# 3_cyber60-2-mcu.net
KiCad netlist of a schematic drawn in Altium Designer
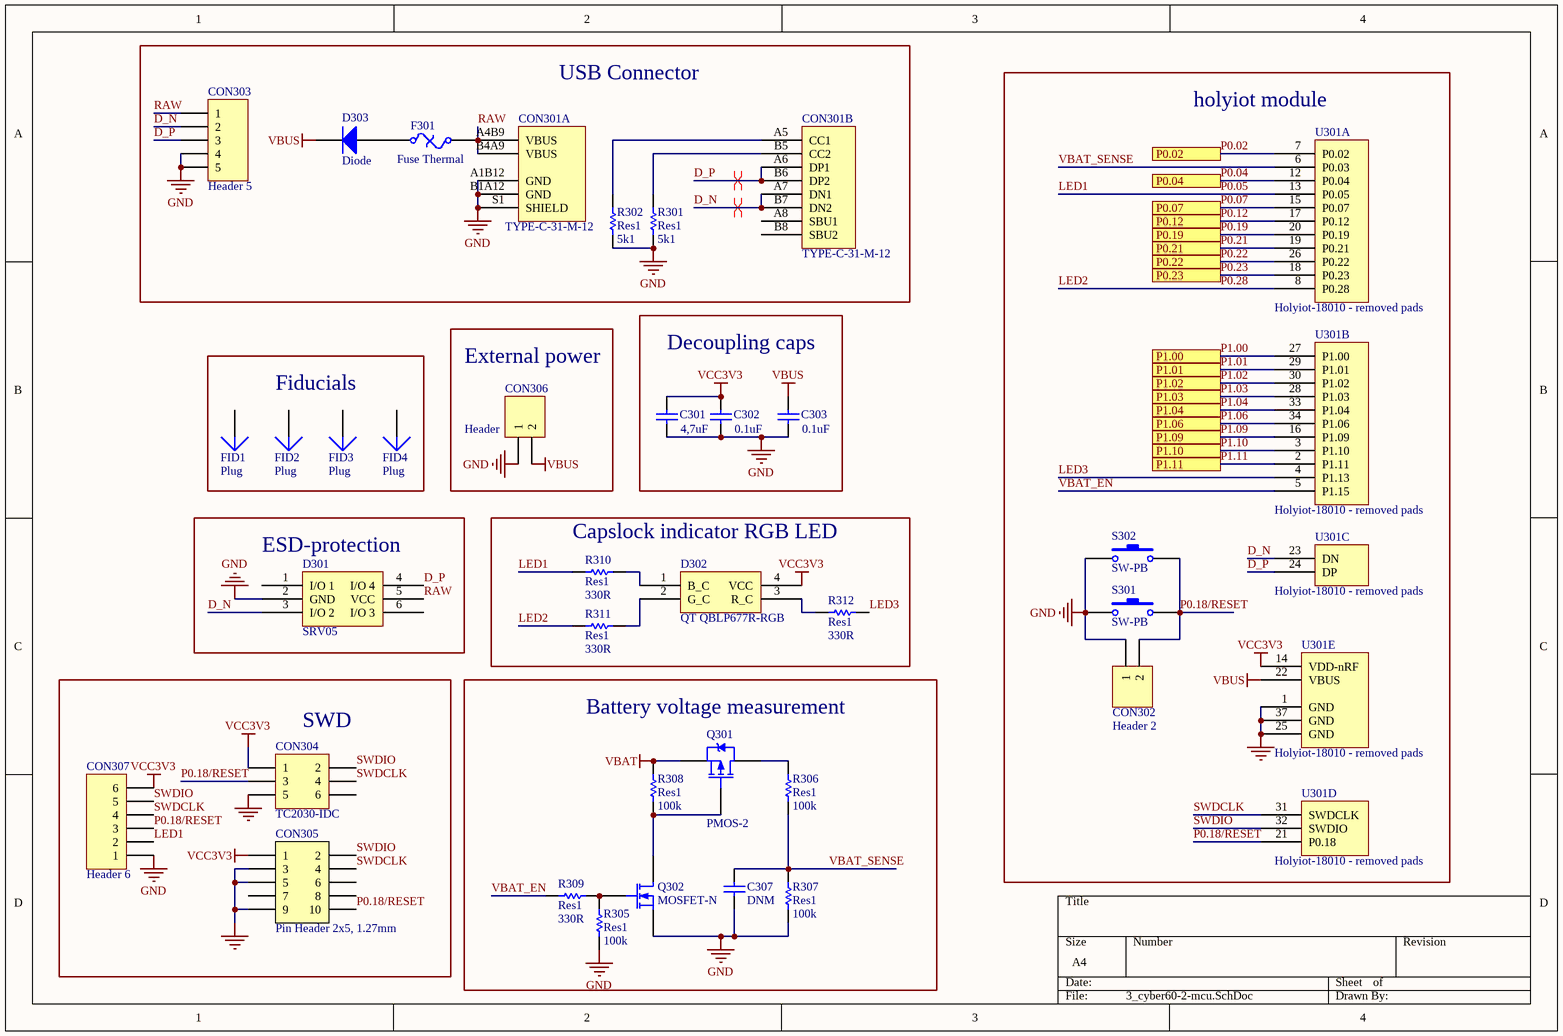
[diagram p0: 3_cyber60-2-mcu.SchDoc]

(export (version "E")
  (design (tool "Eeschema 10.0.6"))
  (components
    (comp (ref "C301")
      (value "4,7uF")
      (footprint "C0603[1608]")
      (description "Capacitor")
      (fields (field (name "LCSC PART #") "C19666") (field (name "MRF.PART") "CL10A475KO8NNNC"))
      (libsource (lib "Miscellaneous Devices") (part "Cap"))
    )
    (comp (ref "C302")
      (value "0.1uF")
      (footprint "C0603[1608]")
      (description "Capacitor")
      (fields (field (name "MFG") "KEMET") (field (name "LCSC PART #") "C14663"))
      (libsource (lib "Miscellaneous Devices") (part "Cap"))
    )
    (comp (ref "C303")
      (value "0.1uF")
      (footprint "C0603[1608]")
      (description "Capacitor")
      (fields (field (name "MFG") "KEMET") (field (name "LCSC PART #") "C14663"))
      (libsource (lib "Miscellaneous Devices") (part "Cap"))
    )
    (comp (ref "C307")
      (value "DNM")
      (footprint "C0603[1608]")
      (description "Capacitor")
      (libsource (lib "Miscellaneous Devices") (part "Cap"))
    )
    (comp (ref "CON301")
      (value "TYPE-C-31-M-12")
      (footprint "TYPE-C-31-M-12")
      (fields (field (name "MFG") "Korean Hroparts Elec") (field (name "LCSC PART #") "C165948"))
      (libsource (lib "Schlib1") (part "TYPE-C-31-M-12"))
    )
    (comp (ref "CON302")
      (value "Header 2")
      (footprint "HDR1X2")
      (description "Header, 2-Pin")
      (libsource (lib "Miscellaneous Connectors") (part "Header 2"))
    )
    (comp (ref "CON303")
      (value "Header 5")
      (footprint "JST SM04B-SRSS-TB")
      (description "JST for USB daughter board")
      (fields (field (name "MFG") "JST Sales America Inc.") (field (name "LCSC PART #") "C160404"))
      (libsource (lib "Miscellaneous Connectors") (part "Header 5"))
    )
    (comp (ref "CON304")
      (value "TC2030-IDC")
      (footprint "TC2030-IDC-NL")
      (description "Header, 3-Pin, Dual row")
      (libsource (lib "Miscellaneous Connectors") (part "Header 3X2"))
    )
    (comp (ref "CON305")
      (value "Pin Header 2x5, 1.27mm")
      (footprint "HDR_2x5-SMD-1.27mm-K")
      (description "Pin Header 2x5, 1.27mm (50mil), SMD, Keying Shroud")
      (fields (field (name "MFG") "Samtec Inc."))
      (libsource (lib "Nordic Passive DB") (part "CONN-2x5"))
    )
    (comp (ref "CON306")
      (value "Header")
      (footprint "HDR1X2")
      (description "Header, 2-Pin")
      (libsource (lib "") (part "Header 2_1"))
    )
    (comp (ref "CON307")
      (value "Header 6")
      (footprint "HDR1X6")
      (description "Header, 6-Pin")
      (fields (field (name "PUBLISHER") "Altium Limited"))
      (libsource (lib "Miscellaneous Connectors") (part "Header 6"))
    )
    (comp (ref "D301")
      (value "SRV05")
      (footprint "SOT-23-6")
      (fields (field (name "LCSC PART #") "C85364") (field (name "MRF.PART") "SRV05-4-P-T7"))
      (libsource (lib "Keebs") (part "SRV05"))
    )
    (comp (ref "D302")
      (value "QT QBLP677R-RGB")
      (footprint "QT QBLP677R-RGB")
      (description "RGB LED")
      (fields (field (name "MFG") "QT Brightek (QTB)"))
      (libsource (lib "Keebs") (part "QT QBLP677R-RGB"))
    )
    (comp (ref "D303")
      (value "Diode")
      (footprint "SOD-123")
      (description "Default Diode")
      (fields (field (name "LCSC PART #") "C8598") (field (name "MRF.PART") "B5819W"))
      (libsource (lib "Miscellaneous Devices") (part "Diode"))
    )
    (comp (ref "F301")
      (value "Fuse Thermal")
      (footprint "C1206[3216]")
      (description "Thermal Fuse")
      (fields (field (name "MFG") "Bel Fuse Inc.") (field (name "LCSC PART #") "C135338"))
      (libsource (lib "Miscellaneous Devices") (part "Fuse Thermal"))
    )
    (comp (ref "FID1")
      (value "Plug")
      (footprint "Fiducial_Nordic")
      (libsource (lib "Miscellaneous Connectors") (part "Plug"))
    )
    (comp (ref "FID2")
      (value "Plug")
      (footprint "Fiducial_Nordic")
      (libsource (lib "Miscellaneous Connectors") (part "Plug"))
    )
    (comp (ref "FID3")
      (value "Plug")
      (footprint "Fiducial_Nordic")
      (libsource (lib "Miscellaneous Connectors") (part "Plug"))
    )
    (comp (ref "FID4")
      (value "Plug")
      (footprint "Fiducial_Nordic")
      (libsource (lib "Miscellaneous Connectors") (part "Plug"))
    )
    (comp (ref "Q301")
      (value "PMOS-2")
      (footprint "SOT-23-3")
      (description "P-Channel Power MOSFET")
      (fields (field (name "MRF.PART") "SI2301CDS-T1-GE3") (field (name "LCSC PART #") "C10487"))
      (libsource (lib "Miscellaneous Devices") (part "PMOS-2"))
    )
    (comp (ref "Q302")
      (value "MOSFET-N")
      (footprint "SOT-23-3")
      (description "N-Channel MOSFET")
      (fields (field (name "LCSC PART #") "C8545") (field (name "MRF.PART") "2N7002"))
      (libsource (lib "Miscellaneous Devices") (part "MOSFET-N"))
    )
    (comp (ref "R301")
      (value "Res1")
      (footprint "R0603[1608]")
      (description "Resistor")
      (fields
        (field (name "ALTIUM_VALUE") "5k1")
        (field (name "MFG") "Panasonic Electronic Components")
        (field (name "LCSC PART #") "C23186")
      )
      (libsource (lib "Miscellaneous Devices") (part "Res1"))
    )
    (comp (ref "R302")
      (value "Res1")
      (footprint "R0603[1608]")
      (description "Resistor")
      (fields
        (field (name "ALTIUM_VALUE") "5k1")
        (field (name "MFG") "Panasonic Electronic Components")
        (field (name "LCSC PART #") "C23186")
      )
      (libsource (lib "Miscellaneous Devices") (part "Res1"))
    )
    (comp (ref "R305")
      (value "Res1")
      (footprint "R0603[1608]")
      (description "Resistor")
      (fields
        (field (name "ALTIUM_VALUE") "100k")
        (field (name "MRF.PART") "0603WAF1003T5E")
        (field (name "LCSC PART #") "C25803")
      )
      (libsource (lib "Miscellaneous Devices") (part "Res1"))
    )
    (comp (ref "R306")
      (value "Res1")
      (footprint "R0603[1608]")
      (description "Resistor")
      (fields
        (field (name "ALTIUM_VALUE") "100k")
        (field (name "MRF.PART") "0603WAF1003T5E")
        (field (name "LCSC PART #") "C25803")
      )
      (libsource (lib "Miscellaneous Devices") (part "Res1"))
    )
    (comp (ref "R307")
      (value "Res1")
      (footprint "R0603[1608]")
      (description "Resistor")
      (fields
        (field (name "ALTIUM_VALUE") "100k")
        (field (name "MRF.PART") "0603WAF1003T5E")
        (field (name "LCSC PART #") "C25803")
      )
      (libsource (lib "Miscellaneous Devices") (part "Res1"))
    )
    (comp (ref "R308")
      (value "Res1")
      (footprint "R0603[1608]")
      (description "Resistor")
      (fields
        (field (name "ALTIUM_VALUE") "100k")
        (field (name "MRF.PART") "0603WAF1003T5E")
        (field (name "LCSC PART #") "C25803")
      )
      (libsource (lib "Miscellaneous Devices") (part "Res1"))
    )
    (comp (ref "R309")
      (value "Res1")
      (footprint "R0603[1608]")
      (description "Resistor")
      (fields
        (field (name "ALTIUM_VALUE") "330R")
        (field (name "LCSC PART #") "C23138")
        (field (name "MRF.PART") "0603WAF3300T5E")
      )
      (libsource (lib "Miscellaneous Devices") (part "Res1"))
    )
    (comp (ref "R310")
      (value "Res1")
      (footprint "R0603[1608]")
      (description "Resistor")
      (fields
        (field (name "ALTIUM_VALUE") "330R")
        (field (name "LCSC PART #") "C23138")
        (field (name "MRF.PART") "0603WAF3300T5E")
      )
      (libsource (lib "Miscellaneous Devices") (part "Res1"))
    )
    (comp (ref "R311")
      (value "Res1")
      (footprint "R0603[1608]")
      (description "Resistor")
      (fields
        (field (name "ALTIUM_VALUE") "330R")
        (field (name "LCSC PART #") "C23138")
        (field (name "MRF.PART") "0603WAF3300T5E")
      )
      (libsource (lib "Miscellaneous Devices") (part "Res1"))
    )
    (comp (ref "R312")
      (value "Res1")
      (footprint "R0603[1608]")
      (description "Resistor")
      (fields
        (field (name "ALTIUM_VALUE") "330R")
        (field (name "LCSC PART #") "C23138")
        (field (name "MRF.PART") "0603WAF3300T5E")
      )
      (libsource (lib "Miscellaneous Devices") (part "Res1"))
    )
    (comp (ref "S301")
      (value "SW-PB")
      (footprint "XKB Switch")
      (description "Switch")
      (fields (field (name "MFG") "C&K") (field (name "MRF.PART") "TS-1187A-C-D-B"))
      (libsource (lib "Miscellaneous Devices") (part "SW-PB"))
    )
    (comp (ref "S302")
      (value "SW-PB")
      (footprint "XKB Switch")
      (description "Switch")
      (fields (field (name "MFG") "C&K") (field (name "MRF.PART") "TS-1187A-C-D-B"))
      (libsource (lib "Miscellaneous Devices") (part "SW-PB"))
    )
    (comp (ref "U301")
      (value "Holyiot-18010 - removed pads")
      (footprint "Holyiot-18010 - removed pads")
      (libsource (lib "Keebs") (part "Holyiot-18010 - removed pads"))
    )
  )
  (nets
    (net (code "1") (name "/D_N") (class "Default")
      (node (ref "CON301") (pin "A7") (pinfunction "DN1_A7") (pintype "passive"))
      (node (ref "CON301") (pin "B7") (pinfunction "DN2_B7") (pintype "passive"))
      (node (ref "CON303") (pin "2") (pinfunction "2_2") (pintype "passive"))
      (node (ref "D301") (pin "3") (pinfunction "I/O_2_3") (pintype "passive"))
      (node (ref "U301") (pin "23") (pinfunction "DN_23") (pintype "passive"))
    )
    (net (code "2") (name "/D_P") (class "Default")
      (node (ref "CON301") (pin "A6") (pinfunction "DP1_A6") (pintype "passive"))
      (node (ref "CON301") (pin "B6") (pinfunction "DP2_B6") (pintype "passive"))
      (node (ref "CON303") (pin "3") (pinfunction "3_3") (pintype "passive"))
      (node (ref "D301") (pin "4") (pinfunction "I/O_4_4") (pintype "passive"))
      (node (ref "U301") (pin "24") (pinfunction "DP_24") (pintype "passive"))
    )
    (net (code "3") (name "/LED1") (class "Default")
      (node (ref "CON307") (pin "2") (pinfunction "2_2") (pintype "passive"))
      (node (ref "R310") (pin "2") (pinfunction "2_2") (pintype "passive"))
      (node (ref "U301") (pin "13") (pinfunction "P0.05_13") (pintype "passive"))
    )
    (net (code "4") (name "/LED2") (class "Default")
      (node (ref "R311") (pin "2") (pinfunction "2_2") (pintype "passive"))
      (node (ref "U301") (pin "8") (pinfunction "P0.28_8") (pintype "passive"))
    )
    (net (code "5") (name "/LED3") (class "Default")
      (node (ref "R312") (pin "1") (pinfunction "1_1") (pintype "passive"))
      (node (ref "U301") (pin "4") (pinfunction "P1.13_4") (pintype "passive"))
    )
    (net (code "6") (name "/P0.02") (class "Default")
      (node (ref "U301") (pin "7") (pinfunction "P0.02_7") (pintype "passive"))
    )
    (net (code "7") (name "/P0.04") (class "Default")
      (node (ref "U301") (pin "12") (pinfunction "P0.04_12") (pintype "passive"))
    )
    (net (code "8") (name "/P0.07") (class "Default")
      (node (ref "U301") (pin "15") (pinfunction "P0.07_15") (pintype "passive"))
    )
    (net (code "9") (name "/P0.12") (class "Default")
      (node (ref "U301") (pin "17") (pinfunction "P0.12_17") (pintype "passive"))
    )
    (net (code "10") (name "/P0.18{slash}RESET") (class "Default")
      (node (ref "CON302") (pin "2") (pinfunction "2_2") (pintype "passive"))
      (node (ref "CON304") (pin "3") (pinfunction "3_3") (pintype "passive"))
      (node (ref "CON305") (pin "10") (pinfunction "10_10") (pintype "passive"))
      (node (ref "CON307") (pin "3") (pinfunction "3_3") (pintype "passive"))
      (node (ref "S301") (pin "2") (pinfunction "2_2") (pintype "passive"))
      (node (ref "S302") (pin "1") (pinfunction "1_1") (pintype "passive"))
      (node (ref "U301") (pin "21") (pinfunction "P0.18_21") (pintype "passive"))
    )
    (net (code "11") (name "/P0.19") (class "Default")
      (node (ref "U301") (pin "20") (pinfunction "P0.19_20") (pintype "passive"))
    )
    (net (code "12") (name "/P0.21") (class "Default")
      (node (ref "U301") (pin "19") (pinfunction "P0.21_19") (pintype "passive"))
    )
    (net (code "13") (name "/P0.22") (class "Default")
      (node (ref "U301") (pin "26") (pinfunction "P0.22_26") (pintype "passive"))
    )
    (net (code "14") (name "/P0.23") (class "Default")
      (node (ref "U301") (pin "18") (pinfunction "P0.23_18") (pintype "passive"))
    )
    (net (code "15") (name "/P1.00") (class "Default")
      (node (ref "U301") (pin "27") (pinfunction "P1.00_27") (pintype "passive"))
    )
    (net (code "16") (name "/P1.01") (class "Default")
      (node (ref "U301") (pin "29") (pinfunction "P1.01_29") (pintype "passive"))
    )
    (net (code "17") (name "/P1.02") (class "Default")
      (node (ref "U301") (pin "30") (pinfunction "P1.02_30") (pintype "passive"))
    )
    (net (code "18") (name "/P1.03") (class "Default")
      (node (ref "U301") (pin "28") (pinfunction "P1.03_28") (pintype "passive"))
    )
    (net (code "19") (name "/P1.04") (class "Default")
      (node (ref "U301") (pin "33") (pinfunction "P1.04_33") (pintype "passive"))
    )
    (net (code "20") (name "/P1.06") (class "Default")
      (node (ref "U301") (pin "34") (pinfunction "P1.06_34") (pintype "passive"))
    )
    (net (code "21") (name "/P1.09") (class "Default")
      (node (ref "U301") (pin "16") (pinfunction "P1.09_16") (pintype "passive"))
    )
    (net (code "22") (name "/P1.10") (class "Default")
      (node (ref "U301") (pin "3") (pinfunction "P1.10_3") (pintype "passive"))
    )
    (net (code "23") (name "/P1.11") (class "Default")
      (node (ref "U301") (pin "2") (pinfunction "P1.11_2") (pintype "passive"))
    )
    (net (code "24") (name "/RAW") (class "Default")
      (node (ref "CON301") (pin "A4B9") (pinfunction "VBUS_A4B9") (pintype "passive"))
      (node (ref "CON301") (pin "B4A9") (pinfunction "VBUS_B4A9") (pintype "passive"))
      (node (ref "CON303") (pin "1") (pinfunction "1_1") (pintype "passive"))
      (node (ref "D301") (pin "5") (pinfunction "VCC_5") (pintype "passive"))
      (node (ref "F301") (pin "2") (pinfunction "2_2") (pintype "passive"))
    )
    (net (code "25") (name "/SWDCLK") (class "Default")
      (node (ref "CON304") (pin "4") (pinfunction "4_4") (pintype "passive"))
      (node (ref "CON305") (pin "4") (pinfunction "4_4") (pintype "passive"))
      (node (ref "CON307") (pin "4") (pinfunction "4_4") (pintype "passive"))
      (node (ref "U301") (pin "31") (pinfunction "SWDCLK_31") (pintype "passive"))
    )
    (net (code "26") (name "/SWDIO") (class "Default")
      (node (ref "CON304") (pin "2") (pinfunction "2_2") (pintype "passive"))
      (node (ref "CON305") (pin "2") (pinfunction "2_2") (pintype "passive"))
      (node (ref "CON307") (pin "5") (pinfunction "5_5") (pintype "passive"))
      (node (ref "U301") (pin "32") (pinfunction "SWDIO_32") (pintype "passive"))
    )
    (net (code "27") (name "/VBAT_EN") (class "Default")
      (node (ref "R309") (pin "2") (pinfunction "2_2") (pintype "passive"))
      (node (ref "U301") (pin "5") (pinfunction "P1.15_5") (pintype "passive"))
    )
    (net (code "28") (name "/VBAT_SENSE") (class "Default")
      (node (ref "C307") (pin "2") (pinfunction "2_2") (pintype "passive"))
      (node (ref "R306") (pin "2") (pinfunction "2_2") (pintype "passive"))
      (node (ref "R307") (pin "1") (pinfunction "1_1") (pintype "passive"))
      (node (ref "U301") (pin "6") (pinfunction "P0.03_6") (pintype "passive"))
    )
    (net (code "29") (name "GND") (class "Default")
      (node (ref "C301") (pin "1") (pinfunction "1_1") (pintype "passive"))
      (node (ref "C302") (pin "1") (pinfunction "1_1") (pintype "passive"))
      (node (ref "C303") (pin "1") (pinfunction "1_1") (pintype "passive"))
      (node (ref "C307") (pin "1") (pinfunction "1_1") (pintype "passive"))
      (node (ref "CON301") (pin "A1B12") (pinfunction "GND_A1B12") (pintype "passive"))
      (node (ref "CON301") (pin "B1A12") (pinfunction "GND_B1A12") (pintype "passive"))
      (node (ref "CON301") (pin "S1") (pinfunction "SHIELD_S1") (pintype "passive"))
      (node (ref "CON302") (pin "1") (pinfunction "1_1") (pintype "passive"))
      (node (ref "CON303") (pin "4") (pinfunction "4_4") (pintype "passive"))
      (node (ref "CON303") (pin "5") (pinfunction "5_5") (pintype "passive"))
      (node (ref "CON304") (pin "5") (pinfunction "5_5") (pintype "passive"))
      (node (ref "CON305") (pin "3") (pinfunction "3_3") (pintype "passive"))
      (node (ref "CON305") (pin "5") (pinfunction "5_5") (pintype "passive"))
      (node (ref "CON305") (pin "9") (pinfunction "9_9") (pintype "passive"))
      (node (ref "CON306") (pin "1") (pinfunction "1_1") (pintype "passive"))
      (node (ref "CON307") (pin "1") (pinfunction "1_1") (pintype "passive"))
      (node (ref "D301") (pin "2") (pinfunction "GND_2") (pintype "passive"))
      (node (ref "Q302") (pin "2") (pinfunction "S_2") (pintype "passive"))
      (node (ref "R301") (pin "2") (pinfunction "2_2") (pintype "passive"))
      (node (ref "R302") (pin "2") (pinfunction "2_2") (pintype "passive"))
      (node (ref "R305") (pin "2") (pinfunction "2_2") (pintype "passive"))
      (node (ref "R307") (pin "2") (pinfunction "2_2") (pintype "passive"))
      (node (ref "S301") (pin "1") (pinfunction "1_1") (pintype "passive"))
      (node (ref "S302") (pin "2") (pinfunction "2_2") (pintype "passive"))
      (node (ref "U301") (pin "1") (pinfunction "GND_1") (pintype "passive"))
      (node (ref "U301") (pin "25") (pinfunction "GND_25") (pintype "passive"))
      (node (ref "U301") (pin "37") (pinfunction "GND_37") (pintype "passive"))
    )
    (net (code "30") (name "Net-(CON301B-CC1)") (class "Default")
      (node (ref "CON301") (pin "A5") (pinfunction "CC1_A5") (pintype "passive"))
      (node (ref "R302") (pin "1") (pinfunction "1_1") (pintype "passive"))
    )
    (net (code "31") (name "Net-(CON301B-CC2)") (class "Default")
      (node (ref "CON301") (pin "B5") (pinfunction "CC2_B5") (pintype "passive"))
      (node (ref "R301") (pin "1") (pinfunction "1_1") (pintype "passive"))
    )
    (net (code "32") (name "Net-(D302-B_C)") (class "Default")
      (node (ref "D302") (pin "1") (pinfunction "B_C_1") (pintype "passive"))
      (node (ref "R310") (pin "1") (pinfunction "1_1") (pintype "passive"))
    )
    (net (code "33") (name "Net-(D302-G_C)") (class "Default")
      (node (ref "D302") (pin "2") (pinfunction "G_C_2") (pintype "passive"))
      (node (ref "R311") (pin "1") (pinfunction "1_1") (pintype "passive"))
    )
    (net (code "34") (name "Net-(D302-R_C)") (class "Default")
      (node (ref "D302") (pin "3") (pinfunction "R_C_3") (pintype "passive"))
      (node (ref "R312") (pin "2") (pinfunction "2_2") (pintype "passive"))
    )
    (net (code "35") (name "Net-(D303-A)") (class "Default")
      (node (ref "D303") (pin "1") (pinfunction "A_1") (pintype "passive"))
      (node (ref "F301") (pin "1") (pinfunction "1_1") (pintype "passive"))
    )
    (net (code "36") (name "Net-(Q301-D)") (class "Default")
      (node (ref "Q301") (pin "3") (pinfunction "D_3") (pintype "passive"))
      (node (ref "R306") (pin "1") (pinfunction "1_1") (pintype "passive"))
    )
    (net (code "37") (name "Net-(Q301-G)") (class "Default")
      (node (ref "Q301") (pin "1") (pinfunction "G_1") (pintype "passive"))
      (node (ref "Q302") (pin "3") (pinfunction "D_3") (pintype "passive"))
      (node (ref "R308") (pin "2") (pinfunction "2_2") (pintype "passive"))
    )
    (net (code "38") (name "Net-(Q302-G)") (class "Default")
      (node (ref "Q302") (pin "1") (pinfunction "G_1") (pintype "passive"))
      (node (ref "R305") (pin "1") (pinfunction "1_1") (pintype "passive"))
      (node (ref "R309") (pin "1") (pinfunction "1_1") (pintype "passive"))
    )
    (net (code "39") (name "VBAT") (class "Default")
      (node (ref "Q301") (pin "2") (pinfunction "S_2") (pintype "passive"))
      (node (ref "R308") (pin "1") (pinfunction "1_1") (pintype "passive"))
    )
    (net (code "40") (name "VBUS") (class "Default")
      (node (ref "C303") (pin "2") (pinfunction "2_2") (pintype "passive"))
      (node (ref "CON306") (pin "2") (pinfunction "2_2") (pintype "passive"))
      (node (ref "D303") (pin "2") (pinfunction "K_2") (pintype "passive"))
      (node (ref "U301") (pin "22") (pinfunction "VBUS_22") (pintype "passive"))
    )
    (net (code "41") (name "VCC3V3") (class "Default")
      (node (ref "C301") (pin "2") (pinfunction "2_2") (pintype "passive"))
      (node (ref "C302") (pin "2") (pinfunction "2_2") (pintype "passive"))
      (node (ref "CON304") (pin "1") (pinfunction "1_1") (pintype "passive"))
      (node (ref "CON305") (pin "1") (pinfunction "1_1") (pintype "passive"))
      (node (ref "CON307") (pin "6") (pinfunction "6_6") (pintype "passive"))
      (node (ref "D302") (pin "4") (pinfunction "VCC_4") (pintype "passive"))
      (node (ref "U301") (pin "14") (pinfunction "VDD-nRF_14") (pintype "passive"))
    )
    (net (code "42") (name "unconnected-(CON301B-SBU1-PadA8)") (class "Default")
      (node (ref "CON301") (pin "A8") (pinfunction "SBU1_A8") (pintype "passive"))
    )
    (net (code "43") (name "unconnected-(CON301B-SBU2-PadB8)") (class "Default")
      (node (ref "CON301") (pin "B8") (pinfunction "SBU2_B8") (pintype "passive"))
    )
    (net (code "44") (name "unconnected-(CON304-Pad6)") (class "Default")
      (node (ref "CON304") (pin "6") (pinfunction "6_6") (pintype "passive"))
    )
    (net (code "45") (name "unconnected-(CON305-Pad6)") (class "Default")
      (node (ref "CON305") (pin "6") (pinfunction "6_6") (pintype "passive"))
    )
    (net (code "46") (name "unconnected-(CON305-Pad7)") (class "Default")
      (node (ref "CON305") (pin "7") (pinfunction "7_7") (pintype "passive"))
    )
    (net (code "47") (name "unconnected-(CON305-Pad8)") (class "Default")
      (node (ref "CON305") (pin "8") (pinfunction "8_8") (pintype "passive"))
    )
    (net (code "48") (name "unconnected-(D301-I{slash}O_1-Pad1)") (class "Default")
      (node (ref "D301") (pin "1") (pinfunction "I/O_1_1") (pintype "passive"))
    )
    (net (code "49") (name "unconnected-(D301-I{slash}O_3-Pad6)") (class "Default")
      (node (ref "D301") (pin "6") (pinfunction "I/O_3_6") (pintype "passive"))
    )
    (net (code "50") (name "unconnected-(FID1-Pad1)") (class "Default")
      (node (ref "FID1") (pin "1") (pinfunction "1_1") (pintype "passive"))
    )
    (net (code "51") (name "unconnected-(FID2-Pad1)") (class "Default")
      (node (ref "FID2") (pin "1") (pinfunction "1_1") (pintype "passive"))
    )
    (net (code "52") (name "unconnected-(FID3-Pad1)") (class "Default")
      (node (ref "FID3") (pin "1") (pinfunction "1_1") (pintype "passive"))
    )
    (net (code "53") (name "unconnected-(FID4-Pad1)") (class "Default")
      (node (ref "FID4") (pin "1") (pinfunction "1_1") (pintype "passive"))
    )
  )
)
